# 7_WiFi.net
KiCad netlist of a schematic drawn in Altium Designer
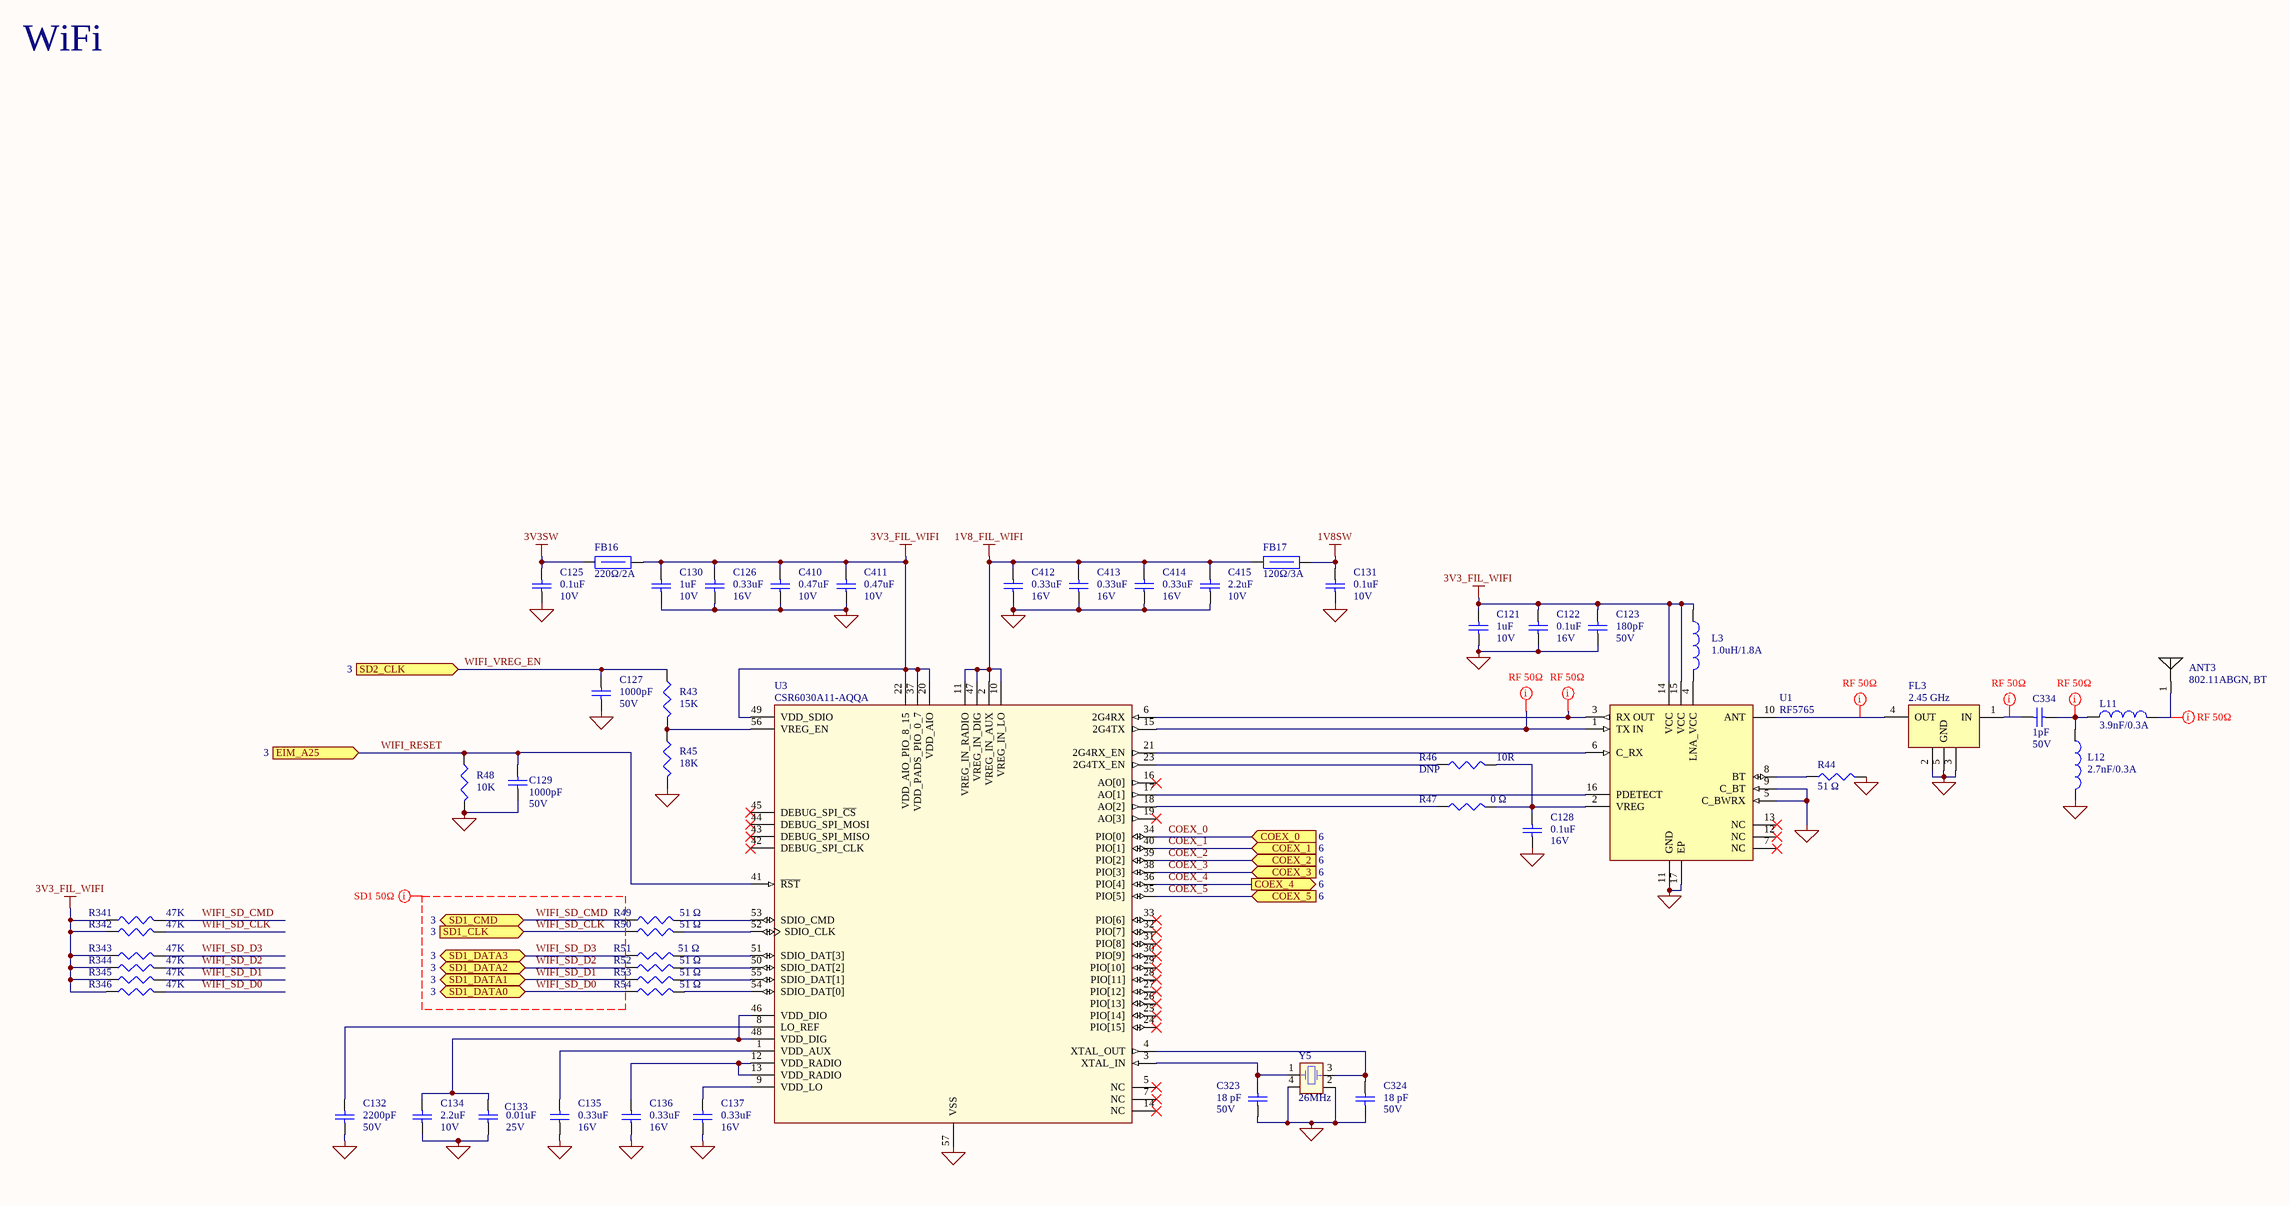
[diagram p0: 7 WiFi.SchDoc]

(export (version "E")
  (design (tool "Eeschema 10.0.6"))
  (components
    (comp (ref "ANT3")
      (value "802.11ABGN, BT")
      (footprint "ANT_2450AT18A100E")
      (description "Antenna, WiFi/BT, SMD")
      (fields
        (field (name "MANUFACTURER") "Johanson Technology, Inc.")
        (field (name "Comment") "2450AT18A100E")
      )
      (libsource (lib "Firstview") (part "2450AT18A100E"))
    )
    (comp (ref "C121")
      (value "1uF")
      (footprint "CAP_0402")
      (description "Cap, Cer, 1uF, 10V, ±10%, X5R, 0402")
      (fields
        (field (name "MANUFACTURER") "Yageo")
        (field (name "VOLTAGE") "10V")
        (field (name "Comment") "Cap 1uF 10V 0402")
      )
      (libsource (lib "Firstview") (part "Cap 1uF 10V 0402"))
    )
    (comp (ref "C122")
      (value "0.1uF")
      (footprint "CAP_0402")
      (description "Cap, Cer, 0.1uF, 16V, 10%, X7R, 0402")
      (fields
        (field (name "TOLERANCE") "±10%")
        (field (name "MANUFACTURER") "Murata Electronics North America")
        (field (name "VOLTAGE") "16V")
      )
      (libsource (lib "Firstview") (part "Cap 0.1uF 16V 0402"))
    )
    (comp (ref "C123")
      (value "180pF")
      (footprint "CAP_0402")
      (description "Cap, Cer, 180pF, 50V, 5%, NP0, 0402")
      (fields
        (field (name "TOLERANCE") "5%")
        (field (name "MANUFACTURER") "Murata Electronics North America")
        (field (name "VOLTAGE") "50V")
      )
      (libsource (lib "Firstview") (part "Cap 180pF 50V 0402"))
    )
    (comp (ref "C125")
      (value "0.1uF")
      (footprint "CAP_0402")
      (description "Cap, Cer, 0.1uF, 10V, 10%, X5R, 0402")
      (fields
        (field (name "TOLERANCE") "±10%")
        (field (name "MANUFACTURER") "Murata Electronics North America")
        (field (name "VOLTAGE") "10V")
      )
      (libsource (lib "Firstview") (part "Cap 0.1uF 10V 0402"))
    )
    (comp (ref "C126")
      (value "0.33uF")
      (footprint "CAP_0402")
      (description "Cap, Cer, 0.33uF, 16V, 10%, X5R, 0402")
      (fields
        (field (name "TOLERANCE") "10%")
        (field (name "MANUFACTURER") "TDK Corporation")
        (field (name "VOLTAGE") "16V")
      )
      (libsource (lib "Firstview") (part "Cap 0.33uF 16V 0402"))
    )
    (comp (ref "C127")
      (value "1000pF")
      (footprint "CAP_0603")
      (description "Cap, Cer, 1000pF, 50V, 10%, X7S, 0603")
      (fields
        (field (name "TOLERANCE") "10%")
        (field (name "MANUFACTURER") "Yageo")
        (field (name "VOLTAGE") "50V")
      )
      (libsource (lib "Firstview") (part "Cap 1000pF 50V 0603"))
    )
    (comp (ref "C128")
      (value "0.1uF")
      (footprint "CAP_0402")
      (description "Cap, Cer, 0.1uF, 16V, 10%, X7R, 0402")
      (fields
        (field (name "TOLERANCE") "±10%")
        (field (name "MANUFACTURER") "Murata Electronics North America")
        (field (name "VOLTAGE") "16V")
      )
      (libsource (lib "Firstview") (part "Cap 0.1uF 16V 0402"))
    )
    (comp (ref "C129")
      (value "1000pF")
      (footprint "CAP_0603")
      (description "Cap, Cer, 1000pF, 50V, 10%, X7S, 0603")
      (fields
        (field (name "TOLERANCE") "10%")
        (field (name "MANUFACTURER") "Yageo")
        (field (name "VOLTAGE") "50V")
      )
      (libsource (lib "Firstview") (part "Cap 1000pF 50V 0603"))
    )
    (comp (ref "C130")
      (value "1uF")
      (footprint "CAP_0402")
      (description "Cap, Cer, 1uF, 10V, ±10%, X5R, 0402")
      (fields
        (field (name "MANUFACTURER") "Yageo")
        (field (name "VOLTAGE") "10V")
        (field (name "Comment") "Cap 1uF 10V 0402")
      )
      (libsource (lib "Firstview") (part "Cap 1uF 10V 0402"))
    )
    (comp (ref "C131")
      (value "0.1uF")
      (footprint "CAP_0402")
      (description "Cap, Cer, 0.1uF, 10V, 10%, X5R, 0402")
      (fields
        (field (name "TOLERANCE") "±10%")
        (field (name "MANUFACTURER") "Murata Electronics North America")
        (field (name "VOLTAGE") "10V")
      )
      (libsource (lib "Firstview") (part "Cap 0.1uF 10V 0402"))
    )
    (comp (ref "C132")
      (value "2200pF")
      (footprint "CAP_0402")
      (description "Cap, Cer, 2200pF, 50V, 5%, X7R, 0402")
      (fields
        (field (name "TOLERANCE") "5%")
        (field (name "MANUFACTURER") "Murata Electronics North America")
        (field (name "VOLTAGE") "50V")
      )
      (libsource (lib "Firstview") (part "Cap 2200pF 50V 0402"))
    )
    (comp (ref "C133")
      (value "0.01uF")
      (footprint "CAP_0402")
      (description "Cap, Cer, 0.01uF, 25V, ±10%, X7R, 0402")
      (fields
        (field (name "TOLERANCE") "±10%")
        (field (name "MANUFACTURER") "Murata")
        (field (name "VOLTAGE") "25V")
      )
      (libsource (lib "Firstview") (part "Cap 0.01uF 50V 0402"))
    )
    (comp (ref "C134")
      (value "2.2uF")
      (footprint "CAP_0402")
      (description "Cap, Cer, 2.2uF, 10V, 10%, X5R, 0402")
      (fields
        (field (name "VOLTAGE") "10V")
        (field (name "MANUFACTURER") "Kemet")
        (field (name "Comment") "Cap 2.2uF 10V 0402")
      )
      (libsource (lib "Firstview") (part "Cap 2.2uF 10V 0402"))
    )
    (comp (ref "C135")
      (value "0.33uF")
      (footprint "CAP_0402")
      (description "Cap, Cer, 0.33uF, 16V, 10%, X5R, 0402")
      (fields
        (field (name "TOLERANCE") "10%")
        (field (name "MANUFACTURER") "TDK Corporation")
        (field (name "VOLTAGE") "16V")
      )
      (libsource (lib "Firstview") (part "Cap 0.33uF 16V 0402"))
    )
    (comp (ref "C136")
      (value "0.33uF")
      (footprint "CAP_0402")
      (description "Cap, Cer, 0.33uF, 16V, 10%, X5R, 0402")
      (fields
        (field (name "TOLERANCE") "10%")
        (field (name "MANUFACTURER") "TDK Corporation")
        (field (name "VOLTAGE") "16V")
      )
      (libsource (lib "Firstview") (part "Cap 0.33uF 16V 0402"))
    )
    (comp (ref "C137")
      (value "0.33uF")
      (footprint "CAP_0402")
      (description "Cap, Cer, 0.33uF, 16V, 10%, X5R, 0402")
      (fields
        (field (name "TOLERANCE") "10%")
        (field (name "MANUFACTURER") "TDK Corporation")
        (field (name "VOLTAGE") "16V")
      )
      (libsource (lib "Firstview") (part "Cap 0.33uF 16V 0402"))
    )
    (comp (ref "C323")
      (value "18 pF")
      (footprint "CAP_0402")
      (description "Cap, Cer, 18pF, 50V, 5%, C0G, 0402")
      (fields
        (field (name "MANUFACTURER") "TDK Corporation")
        (field (name "VOLTAGE") "50V")
        (field (name "Comment") "Cap 18pF 50V 0402")
      )
      (libsource (lib "Firstview") (part "Cap 18pF 50V 0402"))
    )
    (comp (ref "C324")
      (value "18 pF")
      (footprint "CAP_0402")
      (description "Cap, Cer, 18pF, 50V, 5%, C0G, 0402")
      (fields
        (field (name "MANUFACTURER") "TDK Corporation")
        (field (name "VOLTAGE") "50V")
        (field (name "Comment") "Cap 18pF 50V 0402")
      )
      (libsource (lib "Firstview") (part "Cap 18pF 50V 0402"))
    )
    (comp (ref "C334")
      (value "1pF")
      (footprint "CAP_0402")
      (description "Cap, Cer, 0.1uF, 50V, 10%, X5R, 0402")
      (fields
        (field (name "TOLERANCE") "±10%")
        (field (name "MANUFACTURER") "Kemet")
        (field (name "VOLTAGE") "50V")
      )
      (libsource (lib "Firstview") (part "Cap 1pF 50V 0402 RF"))
    )
    (comp (ref "C410")
      (value "0.47uF")
      (footprint "CAP_0402")
      (description "Cap, Cer, 0.47uF, 10V, 10%, X5R, 0402")
      (fields
        (field (name "MANUFACTURER") "TDK Corporation")
        (field (name "TOLERANCE") "±10%")
        (field (name "VOLTAGE") "10V")
      )
      (libsource (lib "Firstview") (part "Cap 0.47uF 10V 0402"))
    )
    (comp (ref "C411")
      (value "0.47uF")
      (footprint "CAP_0402")
      (description "Cap, Cer, 0.47uF, 10V, 10%, X5R, 0402")
      (fields
        (field (name "MANUFACTURER") "TDK Corporation")
        (field (name "TOLERANCE") "±10%")
        (field (name "VOLTAGE") "10V")
      )
      (libsource (lib "Firstview") (part "Cap 0.47uF 10V 0402"))
    )
    (comp (ref "C412")
      (value "0.33uF")
      (footprint "CAP_0402")
      (description "Cap, Cer, 0.33uF, 16V, 10%, X5R, 0402")
      (fields
        (field (name "TOLERANCE") "10%")
        (field (name "MANUFACTURER") "TDK Corporation")
        (field (name "VOLTAGE") "16V")
      )
      (libsource (lib "Firstview") (part "Cap 0.33uF 16V 0402"))
    )
    (comp (ref "C413")
      (value "0.33uF")
      (footprint "CAP_0402")
      (description "Cap, Cer, 0.33uF, 16V, 10%, X5R, 0402")
      (fields
        (field (name "TOLERANCE") "10%")
        (field (name "MANUFACTURER") "TDK Corporation")
        (field (name "VOLTAGE") "16V")
      )
      (libsource (lib "Firstview") (part "Cap 0.33uF 16V 0402"))
    )
    (comp (ref "C414")
      (value "0.33uF")
      (footprint "CAP_0402")
      (description "Cap, Cer, 0.33uF, 16V, 10%, X5R, 0402")
      (fields
        (field (name "TOLERANCE") "10%")
        (field (name "MANUFACTURER") "TDK Corporation")
        (field (name "VOLTAGE") "16V")
      )
      (libsource (lib "Firstview") (part "Cap 0.33uF 16V 0402"))
    )
    (comp (ref "C415")
      (value "2.2uF")
      (footprint "CAP_0402")
      (description "Cap, Cer, 2.2uF, 10V, 10%, X5R, 0402")
      (fields
        (field (name "MANUFACTURER") "Kemet")
        (field (name "VOLTAGE") "10V")
        (field (name "Comment") "Cap 2.2uF 10V 0402")
      )
      (libsource (lib "Firstview") (part "Cap 2.2uF 10V 0402"))
    )
    (comp (ref "FB16")
      (value "220Ω/2A")
      (footprint "IND_0805")
      (description "Ind, Ferrite Bead, 220R, 50mOhm, 2A, 0805")
      (fields (field (name "MANUFACTURER") "Taiyo Yuden") (field (name "Comment") "BKP2125HS221-T"))
      (libsource (lib "Firstview") (part "BKP2125HS221-T"))
    )
    (comp (ref "FB17")
      (value "120Ω/3A")
      (footprint "IND_0603")
      (description "Ind, Ferrite Bead, 120R, 20mOhm, 3A, 0603")
      (fields
        (field (name "MANUFACTURER") "Murata Electronics North America")
        (field (name "Comment") "BLM18KG121TN1D")
      )
      (libsource (lib "Firstview") (part "BLM18KG121TN1D"))
    )
    (comp (ref "FL3")
      (value "2.45 GHz")
      (footprint "SMD(1.3x1.1)_B39252B9430M410")
      (description "Filter, Saw, 2.45 GHz, WLAN, SMD")
      (fields (field (name "MANUFACTURER") "EPCOS (TDK)") (field (name "Comment") "B39252B9430M410"))
      (libsource (lib "Firstview") (part "B39252B9430M410"))
    )
    (comp (ref "L3")
      (value "1.0uH/1.8A")
      (footprint "IND_VLS252010T-1R0N")
      (description "Ind, Power, 1uH, 1.8A, 85mOhm, Shielded, SMD")
      (fields (field (name "TOLERANCE") "±20%") (field (name "MANUFACTURER") "TDK Corporation"))
      (libsource (lib "Firstview") (part "VLS252010T-1R0N"))
    )
    (comp (ref "L11")
      (value "3.9nF/0.3A")
      (footprint "IND_RF_0402")
      (description "Ind, RF, 3.9nH, 0.3A, 220 mOhm, 0402")
      (fields (field (name "MANUFACTURER") "Johanson Technology Inc") (field (name "Comment") "L-07C3N9SV6T"))
      (libsource (lib "Firstview") (part "L-07C3N9SV6T"))
    )
    (comp (ref "L12")
      (value "2.7nF/0.3A")
      (footprint "IND_RF_0402")
      (description "Ind, RF, 2.7nH, 0.3A, 170 mOhm, 0402")
      (fields (field (name "MANUFACTURER") "Johanson Technology Inc") (field (name "Comment") "L-07C2N7SV6T"))
      (libsource (lib "Firstview") (part "L-07C2N7SV6T"))
    )
    (comp (ref "R43")
      (value "15K")
      (footprint "RES_0402")
      (description "Res, 15K, 0.1W, 1%, 0402")
      (fields
        (field (name "MANUFACTURER") "Panasonic Electronic Components")
        (field (name "Comment") "Res 15K 0.1W")
      )
      (libsource (lib "Firstview") (part "Res 15K 0.1W"))
    )
    (comp (ref "R44")
      (value "51 Ω")
      (footprint "RES_0402")
      (description "Res, 51R, 0.063W, 1%, 0402")
      (fields (field (name "MANUFACTURER") "Rohm Semiconductor") (field (name "Comment") "Res 51R 0.063W"))
      (libsource (lib "Firstview") (part "Res 51R 0.063W"))
    )
    (comp (ref "R45")
      (value "18K")
      (footprint "RES_0402")
      (description "Res, 18K, 0.063W, 1%, 0402")
      (fields (field (name "TOLERANCE") "1%") (field (name "MANUFACTURER") "Rohm Semiconductor"))
      (libsource (lib "Firstview") (part "Res 18K 0.063W"))
    )
    (comp (ref "R46")
      (value "10R")
      (footprint "RES_0402")
      (description "Res, 10R, 0.1W, 0402")
      (fields
        (field (name "DNP") "DNP")
        (field (name "MANUFACTURER") "Panasonic Electronic Components")
        (field (name "Comment") "Res 10R 0.1W")
      )
      (libsource (lib "Firstview") (part "Res 10R 0.1W"))
    )
    (comp (ref "R47")
      (value "0 Ω")
      (footprint "RES_0402")
      (description "Res, 0 ohm, 1/16W, 0402")
      (fields (field (name "MANUFACTURER") "Vishay Dale") (field (name "Comment") "Res 0 ohm 0.1W"))
      (libsource (lib "Firstview") (part "Res 0 ohm 0.1W"))
    )
    (comp (ref "R48")
      (value "10K")
      (footprint "RES_0402")
      (description "Res, 10K, 1/16W, 1%, 0402")
      (fields (field (name "MANUFACTURER") "Yageo") (field (name "Comment") "Res 10K 0.063W"))
      (libsource (lib "Firstview") (part "Res 10K 0.063W"))
    )
    (comp (ref "R49")
      (value "51 Ω")
      (footprint "RES_0402")
      (description "Res, 51R, 0.063W, 1%, 0402")
      (fields (field (name "MANUFACTURER") "Rohm Semiconductor") (field (name "Comment") "Res 51R 0.063W"))
      (libsource (lib "Firstview") (part "Res 51R 0.063W"))
    )
    (comp (ref "R50")
      (value "51 Ω")
      (footprint "RES_0402")
      (description "Res, 51R, 0.063W, 1%, 0402")
      (fields (field (name "MANUFACTURER") "Rohm Semiconductor") (field (name "Comment") "Res 51R 0.063W"))
      (libsource (lib "Firstview") (part "Res 51R 0.063W"))
    )
    (comp (ref "R51")
      (value "51 Ω")
      (footprint "RES_0402")
      (description "Res, 51R, 0.063W, 1%, 0402")
      (fields (field (name "MANUFACTURER") "Rohm Semiconductor") (field (name "Comment") "Res 51R 0.063W"))
      (libsource (lib "Firstview") (part "Res 51R 0.063W"))
    )
    (comp (ref "R52")
      (value "51 Ω")
      (footprint "RES_0402")
      (description "Res, 51R, 0.063W, 1%, 0402")
      (fields (field (name "MANUFACTURER") "Rohm Semiconductor") (field (name "Comment") "Res 51R 0.063W"))
      (libsource (lib "Firstview") (part "Res 51R 0.063W"))
    )
    (comp (ref "R53")
      (value "51 Ω")
      (footprint "RES_0402")
      (description "Res, 51R, 0.063W, 1%, 0402")
      (fields (field (name "MANUFACTURER") "Rohm Semiconductor") (field (name "Comment") "Res 51R 0.063W"))
      (libsource (lib "Firstview") (part "Res 51R 0.063W"))
    )
    (comp (ref "R54")
      (value "51 Ω")
      (footprint "RES_0402")
      (description "Res, 51R, 0.063W, 1%, 0402")
      (fields (field (name "MANUFACTURER") "Rohm Semiconductor") (field (name "Comment") "Res 51R 0.063W"))
      (libsource (lib "Firstview") (part "Res 51R 0.063W"))
    )
    (comp (ref "R341")
      (value "47K")
      (footprint "RES_0402")
      (description "Res, 47K, 0.1W, 1%, 0402")
      (fields
        (field (name "MANUFACTURER") "Panasonic Electronic Components")
        (field (name "Comment") "Res 47K 0.1W")
      )
      (libsource (lib "Firstview") (part "Res 47K 0.1W"))
    )
    (comp (ref "R342")
      (value "47K")
      (footprint "RES_0402")
      (description "Res, 47K, 0.1W, 1%, 0402")
      (fields
        (field (name "MANUFACTURER") "Panasonic Electronic Components")
        (field (name "Comment") "Res 47K 0.1W")
      )
      (libsource (lib "Firstview") (part "Res 47K 0.1W"))
    )
    (comp (ref "R343")
      (value "47K")
      (footprint "RES_0402")
      (description "Res, 47K, 0.1W, 1%, 0402")
      (fields
        (field (name "MANUFACTURER") "Panasonic Electronic Components")
        (field (name "Comment") "Res 47K 0.1W")
      )
      (libsource (lib "Firstview") (part "Res 47K 0.1W"))
    )
    (comp (ref "R344")
      (value "47K")
      (footprint "RES_0402")
      (description "Res, 47K, 0.1W, 1%, 0402")
      (fields
        (field (name "MANUFACTURER") "Panasonic Electronic Components")
        (field (name "Comment") "Res 47K 0.1W")
      )
      (libsource (lib "Firstview") (part "Res 47K 0.1W"))
    )
    (comp (ref "R345")
      (value "47K")
      (footprint "RES_0402")
      (description "Res, 47K, 0.1W, 1%, 0402")
      (fields
        (field (name "MANUFACTURER") "Panasonic Electronic Components")
        (field (name "Comment") "Res 47K 0.1W")
      )
      (libsource (lib "Firstview") (part "Res 47K 0.1W"))
    )
    (comp (ref "R346")
      (value "47K")
      (footprint "RES_0402")
      (description "Res, 47K, 0.1W, 1%, 0402")
      (fields
        (field (name "MANUFACTURER") "Panasonic Electronic Components")
        (field (name "Comment") "Res 47K 0.1W")
      )
      (libsource (lib "Firstview") (part "Res 47K 0.1W"))
    )
    (comp (ref "U1")
      (value "RF5765")
      (footprint "QFN-16_RF5765")
      (description "IC, WiFi 802.11b/g/n FEM, 3-4.8V, 2.4-2.5GHz, QFN-16")
      (fields (field (name "MANUFACTURER") "RFMD"))
      (libsource (lib "Firstview") (part "RF5765"))
    )
    (comp (ref "U3")
      (value "CSR6030A11-AQQA")
      (footprint "QFN-56_CSR6030A11-AQQA")
      (description "IC, WiFi, QFN-56")
      (fields (field (name "MANUFACTURER") "CSR PLC"))
      (libsource (lib "Firstview") (part "CSR6030A11-AQQA"))
    )
    (comp (ref "Y5")
      (value "26MHz")
      (footprint "DFN(3.2x2.5)_403I35D26M00000")
      (description "Clock, Crystal, 26MHz, 50ppm, 18pf, -40+85°C, SMD")
      (fields
        (field (name "MANUFACTURER") "CTS-Frequency Controls")
        (field (name "Comment") "403I35D26M00000")
      )
      (libsource (lib "Firstview") (part "403I35D26M00000"))
    )
  )
  (nets
    (net (code "1") (name "/COEX_0") (class "Default")
      (node (ref "U3") (pin "34") (pinfunction "PIO[0]_34") (pintype "bidirectional"))
    )
    (net (code "2") (name "/COEX_1") (class "Default")
      (node (ref "U3") (pin "40") (pinfunction "PIO[1]_40") (pintype "bidirectional"))
    )
    (net (code "3") (name "/COEX_2") (class "Default")
      (node (ref "U3") (pin "39") (pinfunction "PIO[2]_39") (pintype "bidirectional"))
    )
    (net (code "4") (name "/COEX_3") (class "Default")
      (node (ref "U3") (pin "38") (pinfunction "PIO[3]_38") (pintype "bidirectional"))
    )
    (net (code "5") (name "/COEX_4") (class "Default")
      (node (ref "U3") (pin "36") (pinfunction "PIO[4]_36") (pintype "bidirectional"))
    )
    (net (code "6") (name "/COEX_5") (class "Default")
      (node (ref "U3") (pin "35") (pinfunction "PIO[5]_35") (pintype "bidirectional"))
    )
    (net (code "7") (name "/WIFI_RESET") (class "Default")
      (node (ref "C129") (pin "1") (pinfunction "1_1") (pintype "passive"))
      (node (ref "R48") (pin "1") (pinfunction "1_1") (pintype "passive"))
      (node (ref "U3") (pin "41") (pinfunction "~{RST}_41") (pintype "input"))
    )
    (net (code "8") (name "/WIFI_SD_CLK") (class "Default")
      (node (ref "R342") (pin "2") (pinfunction "2_2") (pintype "passive"))
      (node (ref "R50") (pin "1") (pinfunction "1_1") (pintype "passive"))
    )
    (net (code "9") (name "/WIFI_SD_CMD") (class "Default")
      (node (ref "R341") (pin "2") (pinfunction "2_2") (pintype "passive"))
      (node (ref "R49") (pin "1") (pinfunction "1_1") (pintype "passive"))
    )
    (net (code "10") (name "/WIFI_SD_D0") (class "Default")
      (node (ref "R346") (pin "2") (pinfunction "2_2") (pintype "passive"))
      (node (ref "R54") (pin "1") (pinfunction "1_1") (pintype "passive"))
    )
    (net (code "11") (name "/WIFI_SD_D1") (class "Default")
      (node (ref "R345") (pin "2") (pinfunction "2_2") (pintype "passive"))
      (node (ref "R53") (pin "1") (pinfunction "1_1") (pintype "passive"))
    )
    (net (code "12") (name "/WIFI_SD_D2") (class "Default")
      (node (ref "R344") (pin "2") (pinfunction "2_2") (pintype "passive"))
      (node (ref "R52") (pin "1") (pinfunction "1_1") (pintype "passive"))
    )
    (net (code "13") (name "/WIFI_SD_D3") (class "Default")
      (node (ref "R343") (pin "2") (pinfunction "2_2") (pintype "passive"))
      (node (ref "R51") (pin "1") (pinfunction "1_1") (pintype "passive"))
    )
    (net (code "14") (name "/WIFI_VREG_EN") (class "Default")
      (node (ref "C127") (pin "1") (pinfunction "1_1") (pintype "passive"))
      (node (ref "R43") (pin "1") (pinfunction "1_1") (pintype "passive"))
    )
    (net (code "15") (name "1V8SW") (class "Default")
      (node (ref "C131") (pin "1") (pinfunction "1_1") (pintype "passive"))
      (node (ref "FB17") (pin "2") (pinfunction "2_2") (pintype "passive"))
    )
    (net (code "16") (name "1V8_FIL_WIFI") (class "Default")
      (node (ref "C412") (pin "1") (pinfunction "1_1") (pintype "passive"))
      (node (ref "C413") (pin "1") (pinfunction "1_1") (pintype "passive"))
      (node (ref "C414") (pin "1") (pinfunction "1_1") (pintype "passive"))
      (node (ref "C415") (pin "1") (pinfunction "1_1") (pintype "passive"))
      (node (ref "FB17") (pin "1") (pinfunction "1_1") (pintype "passive"))
      (node (ref "U3") (pin "10") (pinfunction "VREG_IN_LO_10") (pintype "passive"))
      (node (ref "U3") (pin "11") (pinfunction "VREG_IN_RADIO_11") (pintype "passive"))
      (node (ref "U3") (pin "2") (pinfunction "VREG_IN_AUX_2") (pintype "passive"))
      (node (ref "U3") (pin "47") (pinfunction "VREG_IN_DIG_47") (pintype "power_in"))
    )
    (net (code "17") (name "3V3SW") (class "Default")
      (node (ref "C125") (pin "1") (pinfunction "1_1") (pintype "passive"))
      (node (ref "FB16") (pin "1") (pinfunction "1_1") (pintype "passive"))
    )
    (net (code "18") (name "3V3_FIL_WIFI") (class "Default")
      (node (ref "C121") (pin "1") (pinfunction "1_1") (pintype "passive"))
      (node (ref "C122") (pin "1") (pinfunction "1_1") (pintype "passive"))
      (node (ref "C123") (pin "1") (pinfunction "1_1") (pintype "passive"))
      (node (ref "C126") (pin "1") (pinfunction "1_1") (pintype "passive"))
      (node (ref "C130") (pin "1") (pinfunction "1_1") (pintype "passive"))
      (node (ref "C410") (pin "1") (pinfunction "1_1") (pintype "passive"))
      (node (ref "C411") (pin "1") (pinfunction "1_1") (pintype "passive"))
      (node (ref "FB16") (pin "2") (pinfunction "2_2") (pintype "passive"))
      (node (ref "L3") (pin "1") (pinfunction "1_1") (pintype "passive"))
      (node (ref "R341") (pin "1") (pinfunction "1_1") (pintype "passive"))
      (node (ref "R342") (pin "1") (pinfunction "1_1") (pintype "passive"))
      (node (ref "R343") (pin "1") (pinfunction "1_1") (pintype "passive"))
      (node (ref "R344") (pin "1") (pinfunction "1_1") (pintype "passive"))
      (node (ref "R345") (pin "1") (pinfunction "1_1") (pintype "passive"))
      (node (ref "R346") (pin "1") (pinfunction "1_1") (pintype "passive"))
      (node (ref "U1") (pin "14") (pinfunction "VCC_14") (pintype "power_in"))
      (node (ref "U1") (pin "15") (pinfunction "VCC_15") (pintype "power_in"))
      (node (ref "U3") (pin "20") (pinfunction "VDD_AIO_20") (pintype "passive"))
      (node (ref "U3") (pin "22") (pinfunction "VDD_AIO_PIO_8_15_22") (pintype "power_in"))
      (node (ref "U3") (pin "37") (pinfunction "VDD_PADS_PIO_0_7_37") (pintype "power_in"))
      (node (ref "U3") (pin "49") (pinfunction "VDD_SDIO_49") (pintype "power_in"))
    )
    (net (code "19") (name "GND") (class "Default")
      (node (ref "C121") (pin "2") (pinfunction "2_2") (pintype "passive"))
      (node (ref "C122") (pin "2") (pinfunction "2_2") (pintype "passive"))
      (node (ref "C123") (pin "2") (pinfunction "2_2") (pintype "passive"))
      (node (ref "C125") (pin "2") (pinfunction "2_2") (pintype "passive"))
      (node (ref "C126") (pin "2") (pinfunction "2_2") (pintype "passive"))
      (node (ref "C127") (pin "2") (pinfunction "2_2") (pintype "passive"))
      (node (ref "C128") (pin "2") (pinfunction "2_2") (pintype "passive"))
      (node (ref "C129") (pin "2") (pinfunction "2_2") (pintype "passive"))
      (node (ref "C130") (pin "2") (pinfunction "2_2") (pintype "passive"))
      (node (ref "C131") (pin "2") (pinfunction "2_2") (pintype "passive"))
      (node (ref "C132") (pin "2") (pinfunction "2_2") (pintype "passive"))
      (node (ref "C133") (pin "2") (pinfunction "2_2") (pintype "passive"))
      (node (ref "C134") (pin "2") (pinfunction "2_2") (pintype "passive"))
      (node (ref "C135") (pin "2") (pinfunction "2_2") (pintype "passive"))
      (node (ref "C136") (pin "2") (pinfunction "2_2") (pintype "passive"))
      (node (ref "C137") (pin "2") (pinfunction "2_2") (pintype "passive"))
      (node (ref "C323") (pin "2") (pinfunction "2_2") (pintype "passive"))
      (node (ref "C324") (pin "2") (pinfunction "2_2") (pintype "passive"))
      (node (ref "C410") (pin "2") (pinfunction "2_2") (pintype "passive"))
      (node (ref "C411") (pin "2") (pinfunction "2_2") (pintype "passive"))
      (node (ref "C412") (pin "2") (pinfunction "2_2") (pintype "passive"))
      (node (ref "C413") (pin "2") (pinfunction "2_2") (pintype "passive"))
      (node (ref "C414") (pin "2") (pinfunction "2_2") (pintype "passive"))
      (node (ref "C415") (pin "2") (pinfunction "2_2") (pintype "passive"))
      (node (ref "FL3") (pin "2") (pinfunction "GND_2") (pintype "power_in"))
      (node (ref "FL3") (pin "3") (pinfunction "GND_3") (pintype "power_in"))
      (node (ref "FL3") (pin "5") (pinfunction "GND_5") (pintype "power_in"))
      (node (ref "L12") (pin "2") (pinfunction "2_2") (pintype "passive"))
      (node (ref "R44") (pin "2") (pinfunction "2_2") (pintype "passive"))
      (node (ref "R45") (pin "2") (pinfunction "2_2") (pintype "passive"))
      (node (ref "R48") (pin "2") (pinfunction "2_2") (pintype "passive"))
      (node (ref "U1") (pin "11") (pinfunction "GND_11") (pintype "passive"))
      (node (ref "U1") (pin "17") (pinfunction "EP_17") (pintype "passive"))
      (node (ref "U1") (pin "5") (pinfunction "C_BWRX_5") (pintype "input"))
      (node (ref "U1") (pin "9") (pinfunction "C_BT_9") (pintype "input"))
      (node (ref "U3") (pin "57") (pinfunction "VSS_57") (pintype "passive"))
      (node (ref "Y5") (pin "2") (pintype "passive"))
      (node (ref "Y5") (pin "4") (pintype "passive"))
    )
    (net (code "20") (name "Net-(ANT3-Pad1)") (class "Default")
      (node (ref "ANT3") (pin "1") (pinfunction "1_1") (pintype "passive"))
      (node (ref "L11") (pin "2") (pinfunction "2_2") (pintype "passive"))
    )
    (net (code "21") (name "Net-(C136-Pad1)") (class "Default")
      (node (ref "C136") (pin "1") (pinfunction "1_1") (pintype "passive"))
      (node (ref "U3") (pin "12") (pinfunction "VDD_RADIO_12") (pintype "power_in"))
      (node (ref "U3") (pin "13") (pinfunction "VDD_RADIO_13") (pintype "power_in"))
    )
    (net (code "22") (name "Net-(C334-Pad2)") (class "Default")
      (node (ref "C334") (pin "2") (pinfunction "2_2") (pintype "passive"))
      (node (ref "L11") (pin "1") (pinfunction "1_1") (pintype "passive"))
      (node (ref "L12") (pin "1") (pinfunction "1_1") (pintype "passive"))
    )
    (net (code "23") (name "Net-(FL3-IN)") (class "Default")
      (node (ref "C334") (pin "1") (pinfunction "1_1") (pintype "passive"))
      (node (ref "FL3") (pin "1") (pinfunction "IN_1") (pintype "power_in"))
    )
    (net (code "24") (name "Net-(FL3-OUT)") (class "Default")
      (node (ref "FL3") (pin "4") (pinfunction "OUT_4") (pintype "power_in"))
      (node (ref "U1") (pin "10") (pinfunction "ANT_10") (pintype "passive"))
    )
    (net (code "25") (name "Net-(U1-BT)") (class "Default")
      (node (ref "R44") (pin "1") (pinfunction "1_1") (pintype "passive"))
      (node (ref "U1") (pin "8") (pinfunction "BT_8") (pintype "bidirectional"))
    )
    (net (code "26") (name "Net-(U1-C_RX)") (class "Default")
      (node (ref "U1") (pin "6") (pinfunction "C_RX_6") (pintype "input"))
      (node (ref "U3") (pin "21") (pinfunction "2G4RX_EN_21") (pintype "output"))
    )
    (net (code "27") (name "Net-(U1-LNA_VCC)") (class "Default")
      (node (ref "L3") (pin "2") (pinfunction "2_2") (pintype "passive"))
      (node (ref "U1") (pin "4") (pinfunction "LNA_VCC_4") (pintype "power_in"))
    )
    (net (code "28") (name "Net-(U1-PDETECT)") (class "Default")
      (node (ref "U1") (pin "16") (pinfunction "PDETECT_16") (pintype "passive"))
      (node (ref "U3") (pin "17") (pinfunction "AO[1]_17") (pintype "output"))
    )
    (net (code "29") (name "Net-(U1-RX_OUT)") (class "Default")
      (node (ref "U1") (pin "3") (pinfunction "RX_OUT_3") (pintype "output"))
      (node (ref "U3") (pin "6") (pinfunction "2G4RX_6") (pintype "input"))
    )
    (net (code "30") (name "Net-(U1-TX_IN)") (class "Default")
      (node (ref "U1") (pin "1") (pinfunction "TX_IN_1") (pintype "input"))
      (node (ref "U3") (pin "15") (pinfunction "2G4TX_15") (pintype "output"))
    )
    (net (code "31") (name "Net-(U1-VREG)") (class "Default")
      (node (ref "C128") (pin "1") (pinfunction "1_1") (pintype "passive"))
      (node (ref "R46") (pin "2") (pinfunction "2_2") (pintype "passive"))
      (node (ref "R47") (pin "2") (pinfunction "2_2") (pintype "passive"))
      (node (ref "U1") (pin "2") (pinfunction "VREG_2") (pintype "power_in"))
    )
    (net (code "32") (name "Net-(U3-2G4TX_EN)") (class "Default")
      (node (ref "R46") (pin "1") (pinfunction "1_1") (pintype "passive"))
      (node (ref "U3") (pin "23") (pinfunction "2G4TX_EN_23") (pintype "output"))
    )
    (net (code "33") (name "Net-(U3-AO[2])") (class "Default")
      (node (ref "R47") (pin "1") (pinfunction "1_1") (pintype "passive"))
      (node (ref "U3") (pin "18") (pinfunction "AO[2]_18") (pintype "output"))
    )
    (net (code "34") (name "Net-(U3-LO_REF)") (class "Default")
      (node (ref "C132") (pin "1") (pinfunction "1_1") (pintype "passive"))
      (node (ref "U3") (pin "8") (pinfunction "LO_REF_8") (pintype "passive"))
    )
    (net (code "35") (name "Net-(U3-SDIO_CLK)") (class "Default")
      (node (ref "R50") (pin "2") (pinfunction "2_2") (pintype "passive"))
      (node (ref "U3") (pin "52") (pinfunction "SDIO_CLK_52") (pintype "bidirectional"))
    )
    (net (code "36") (name "Net-(U3-SDIO_CMD)") (class "Default")
      (node (ref "R49") (pin "2") (pinfunction "2_2") (pintype "passive"))
      (node (ref "U3") (pin "53") (pinfunction "SDIO_CMD_53") (pintype "bidirectional"))
    )
    (net (code "37") (name "Net-(U3-SDIO_DAT[0])") (class "Default")
      (node (ref "R54") (pin "2") (pinfunction "2_2") (pintype "passive"))
      (node (ref "U3") (pin "54") (pinfunction "SDIO_DAT[0]_54") (pintype "bidirectional"))
    )
    (net (code "38") (name "Net-(U3-SDIO_DAT[1])") (class "Default")
      (node (ref "R53") (pin "2") (pinfunction "2_2") (pintype "passive"))
      (node (ref "U3") (pin "55") (pinfunction "SDIO_DAT[1]_55") (pintype "bidirectional"))
    )
    (net (code "39") (name "Net-(U3-SDIO_DAT[2])") (class "Default")
      (node (ref "R52") (pin "2") (pinfunction "2_2") (pintype "passive"))
      (node (ref "U3") (pin "50") (pinfunction "SDIO_DAT[2]_50") (pintype "bidirectional"))
    )
    (net (code "40") (name "Net-(U3-SDIO_DAT[3])") (class "Default")
      (node (ref "R51") (pin "2") (pinfunction "2_2") (pintype "passive"))
      (node (ref "U3") (pin "51") (pinfunction "SDIO_DAT[3]_51") (pintype "bidirectional"))
    )
    (net (code "41") (name "Net-(U3-VDD_AUX)") (class "Default")
      (node (ref "C135") (pin "1") (pinfunction "1_1") (pintype "passive"))
      (node (ref "U3") (pin "1") (pinfunction "VDD_AUX_1") (pintype "power_in"))
    )
    (net (code "42") (name "Net-(U3-VDD_DIG)") (class "Default")
      (node (ref "C133") (pin "1") (pinfunction "1_1") (pintype "passive"))
      (node (ref "C134") (pin "1") (pinfunction "1_1") (pintype "passive"))
      (node (ref "U3") (pin "46") (pinfunction "VDD_DIO_46") (pintype "passive"))
      (node (ref "U3") (pin "48") (pinfunction "VDD_DIG_48") (pintype "passive"))
    )
    (net (code "43") (name "Net-(U3-VDD_LO)") (class "Default")
      (node (ref "C137") (pin "1") (pinfunction "1_1") (pintype "passive"))
      (node (ref "U3") (pin "9") (pinfunction "VDD_LO_9") (pintype "power_in"))
    )
    (net (code "44") (name "Net-(U3-VREG_EN)") (class "Default")
      (node (ref "R43") (pin "2") (pinfunction "2_2") (pintype "passive"))
      (node (ref "R45") (pin "1") (pinfunction "1_1") (pintype "passive"))
      (node (ref "U3") (pin "56") (pinfunction "VREG_EN_56") (pintype "power_in"))
    )
    (net (code "45") (name "Net-(U3-XTAL_IN)") (class "Default")
      (node (ref "C323") (pin "1") (pinfunction "1_1") (pintype "passive"))
      (node (ref "U3") (pin "3") (pinfunction "XTAL_IN_3") (pintype "input"))
      (node (ref "Y5") (pin "1") (pinfunction "OSC1_1") (pintype "passive"))
    )
    (net (code "46") (name "Net-(U3-XTAL_OUT)") (class "Default")
      (node (ref "C324") (pin "1") (pinfunction "1_1") (pintype "passive"))
      (node (ref "U3") (pin "4") (pinfunction "XTAL_OUT_4") (pintype "output"))
      (node (ref "Y5") (pin "3") (pinfunction "OSC2_3") (pintype "passive"))
    )
    (net (code "47") (name "unconnected-(U1-NC-Pad7)") (class "Default")
      (node (ref "U1") (pin "7") (pinfunction "NC_7") (pintype "passive+no_connect"))
    )
    (net (code "48") (name "unconnected-(U1-NC-Pad12)") (class "Default")
      (node (ref "U1") (pin "12") (pinfunction "NC_12") (pintype "passive+no_connect"))
    )
    (net (code "49") (name "unconnected-(U1-NC-Pad13)") (class "Default")
      (node (ref "U1") (pin "13") (pinfunction "NC_13") (pintype "passive+no_connect"))
    )
    (net (code "50") (name "unconnected-(U3-AO[0]-Pad16)") (class "Default")
      (node (ref "U3") (pin "16") (pinfunction "AO[0]_16") (pintype "output+no_connect"))
    )
    (net (code "51") (name "unconnected-(U3-AO[3]-Pad19)") (class "Default")
      (node (ref "U3") (pin "19") (pinfunction "AO[3]_19") (pintype "output+no_connect"))
    )
    (net (code "52") (name "unconnected-(U3-DEBUG_SPI_CLK-Pad42)") (class "Default")
      (node (ref "U3") (pin "42") (pinfunction "DEBUG_SPI_CLK_42") (pintype "passive+no_connect"))
    )
    (net (code "53") (name "unconnected-(U3-DEBUG_SPI_MISO-Pad43)") (class "Default")
      (node (ref "U3") (pin "43") (pinfunction "DEBUG_SPI_MISO_43") (pintype "passive+no_connect"))
    )
    (net (code "54") (name "unconnected-(U3-DEBUG_SPI_MOSI-Pad44)") (class "Default")
      (node (ref "U3") (pin "44") (pinfunction "DEBUG_SPI_MOSI_44") (pintype "passive+no_connect"))
    )
    (net (code "55") (name "unconnected-(U3-DEBUG_SPI_~{CS}-Pad45)") (class "Default")
      (node (ref "U3") (pin "45") (pinfunction "DEBUG_SPI_~{CS}_45") (pintype "passive+no_connect"))
    )
    (net (code "56") (name "unconnected-(U3-NC-Pad5)") (class "Default")
      (node (ref "U3") (pin "5") (pinfunction "NC_5") (pintype "passive+no_connect"))
    )
    (net (code "57") (name "unconnected-(U3-NC-Pad7)") (class "Default")
      (node (ref "U3") (pin "7") (pinfunction "NC_7") (pintype "passive+no_connect"))
    )
    (net (code "58") (name "unconnected-(U3-NC-Pad14)") (class "Default")
      (node (ref "U3") (pin "14") (pinfunction "NC_14") (pintype "passive+no_connect"))
    )
    (net (code "59") (name "unconnected-(U3-PIO[6]-Pad33)") (class "Default")
      (node (ref "U3") (pin "33") (pinfunction "PIO[6]_33") (pintype "bidirectional+no_connect"))
    )
    (net (code "60") (name "unconnected-(U3-PIO[7]-Pad32)") (class "Default")
      (node (ref "U3") (pin "32") (pinfunction "PIO[7]_32") (pintype "bidirectional+no_connect"))
    )
    (net (code "61") (name "unconnected-(U3-PIO[8]-Pad31)") (class "Default")
      (node (ref "U3") (pin "31") (pinfunction "PIO[8]_31") (pintype "bidirectional+no_connect"))
    )
    (net (code "62") (name "unconnected-(U3-PIO[9]-Pad30)") (class "Default")
      (node (ref "U3") (pin "30") (pinfunction "PIO[9]_30") (pintype "bidirectional+no_connect"))
    )
    (net (code "63") (name "unconnected-(U3-PIO[10]-Pad29)") (class "Default")
      (node (ref "U3") (pin "29") (pinfunction "PIO[10]_29") (pintype "bidirectional+no_connect"))
    )
    (net (code "64") (name "unconnected-(U3-PIO[11]-Pad28)") (class "Default")
      (node (ref "U3") (pin "28") (pinfunction "PIO[11]_28") (pintype "bidirectional+no_connect"))
    )
    (net (code "65") (name "unconnected-(U3-PIO[12]-Pad27)") (class "Default")
      (node (ref "U3") (pin "27") (pinfunction "PIO[12]_27") (pintype "bidirectional+no_connect"))
    )
    (net (code "66") (name "unconnected-(U3-PIO[13]-Pad26)") (class "Default")
      (node (ref "U3") (pin "26") (pinfunction "PIO[13]_26") (pintype "bidirectional+no_connect"))
    )
    (net (code "67") (name "unconnected-(U3-PIO[14]-Pad25)") (class "Default")
      (node (ref "U3") (pin "25") (pinfunction "PIO[14]_25") (pintype "bidirectional+no_connect"))
    )
    (net (code "68") (name "unconnected-(U3-PIO[15]-Pad24)") (class "Default")
      (node (ref "U3") (pin "24") (pinfunction "PIO[15]_24") (pintype "bidirectional+no_connect"))
    )
  )
)
